# tangnano9k-bob-adapter.net
KiCad netlist of a schematic drawn in EAGLE
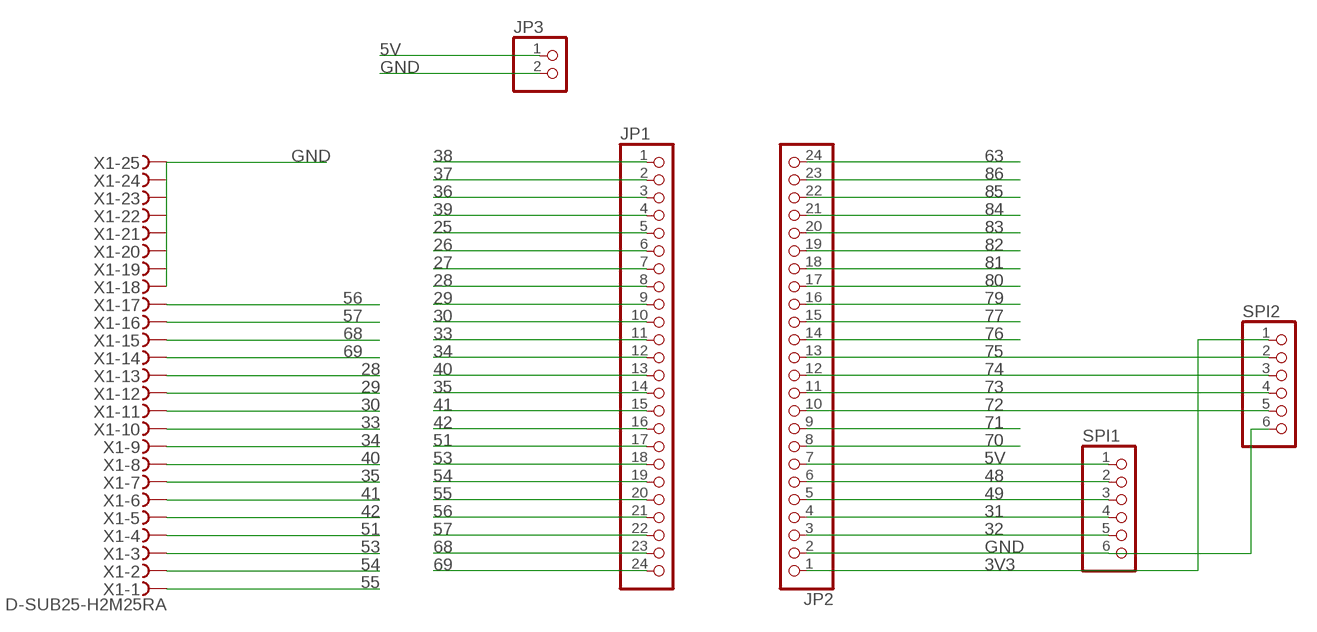
[diagram p0: schematic, sheet 1]

(export (version "E")
  (design (tool "Eeschema 10.0.6"))
  (components
    (comp (ref "JP1")
      (value "PINHD-1X24")
      (footprint "eagle-import:1X24")
      (libsource (lib "eagle-import") (part "PINHD-1X24"))
    )
    (comp (ref "JP2")
      (value "PINHD-1X24")
      (footprint "eagle-import:1X24")
      (libsource (lib "eagle-import") (part "PINHD-1X24"))
    )
    (comp (ref "JP3")
      (value "PINHD-1X2")
      (footprint "eagle-import:1X02")
      (libsource (lib "eagle-import") (part "PINHD-1X2"))
    )
    (comp (ref "SPI1")
      (value "PINHD-1X6")
      (footprint "eagle-import:1X06")
      (libsource (lib "eagle-import") (part "PINHD-1X6"))
    )
    (comp (ref "SPI2")
      (value "PINHD-1X6")
      (footprint "eagle-import:1X06")
      (libsource (lib "eagle-import") (part "PINHD-1X6"))
    )
    (comp (ref "X1")
      (value "D-SUB25-H2M25RA")
      (footprint "eagle-import:H2M25RA")
      (libsource (lib "eagle-import") (part "D-SUB25-H2M25RA"))
    )
  )
  (nets
    (net (code "1") (name "/3V3") (class "Default")
      (node (ref "JP2") (pin "1") (pinfunction "1_1") (pintype "passive"))
      (node (ref "SPI2") (pin "1") (pinfunction "1_1") (pintype "passive"))
    )
    (net (code "2") (name "/5V") (class "Default")
      (node (ref "JP2") (pin "7") (pinfunction "7_7") (pintype "passive"))
      (node (ref "JP3") (pin "1") (pinfunction "1_1") (pintype "passive"))
      (node (ref "SPI1") (pin "1") (pinfunction "1_1") (pintype "passive"))
    )
    (net (code "3") (name "/25") (class "Default")
      (node (ref "JP1") (pin "5") (pinfunction "5_5") (pintype "passive"))
    )
    (net (code "4") (name "/26") (class "Default")
      (node (ref "JP1") (pin "6") (pinfunction "6_6") (pintype "passive"))
    )
    (net (code "5") (name "/27") (class "Default")
      (node (ref "JP1") (pin "7") (pinfunction "7_7") (pintype "passive"))
    )
    (net (code "6") (name "/28") (class "Default")
      (node (ref "JP1") (pin "8") (pinfunction "8_8") (pintype "passive"))
      (node (ref "X1") (pin "13") (pinfunction "F_13") (pintype "passive"))
    )
    (net (code "7") (name "/29") (class "Default")
      (node (ref "JP1") (pin "9") (pinfunction "9_9") (pintype "passive"))
      (node (ref "X1") (pin "12") (pinfunction "F_12") (pintype "passive"))
    )
    (net (code "8") (name "/30") (class "Default")
      (node (ref "JP1") (pin "10") (pinfunction "10_10") (pintype "passive"))
      (node (ref "X1") (pin "11") (pinfunction "F_11") (pintype "passive"))
    )
    (net (code "9") (name "/31") (class "Default")
      (node (ref "JP2") (pin "4") (pinfunction "4_4") (pintype "passive"))
      (node (ref "SPI1") (pin "4") (pinfunction "4_4") (pintype "passive"))
    )
    (net (code "10") (name "/32") (class "Default")
      (node (ref "JP2") (pin "3") (pinfunction "3_3") (pintype "passive"))
      (node (ref "SPI1") (pin "5") (pinfunction "5_5") (pintype "passive"))
    )
    (net (code "11") (name "/33") (class "Default")
      (node (ref "JP1") (pin "11") (pinfunction "11_11") (pintype "passive"))
      (node (ref "X1") (pin "10") (pinfunction "F_10") (pintype "passive"))
    )
    (net (code "12") (name "/34") (class "Default")
      (node (ref "JP1") (pin "12") (pinfunction "12_12") (pintype "passive"))
      (node (ref "X1") (pin "9") (pinfunction "F_9") (pintype "passive"))
    )
    (net (code "13") (name "/35") (class "Default")
      (node (ref "JP1") (pin "14") (pinfunction "14_14") (pintype "passive"))
      (node (ref "X1") (pin "7") (pinfunction "F_7") (pintype "passive"))
    )
    (net (code "14") (name "/36") (class "Default")
      (node (ref "JP1") (pin "3") (pinfunction "3_3") (pintype "passive"))
    )
    (net (code "15") (name "/37") (class "Default")
      (node (ref "JP1") (pin "2") (pinfunction "2_2") (pintype "passive"))
    )
    (net (code "16") (name "/38") (class "Default")
      (node (ref "JP1") (pin "1") (pinfunction "1_1") (pintype "passive"))
    )
    (net (code "17") (name "/39") (class "Default")
      (node (ref "JP1") (pin "4") (pinfunction "4_4") (pintype "passive"))
    )
    (net (code "18") (name "/40") (class "Default")
      (node (ref "JP1") (pin "13") (pinfunction "13_13") (pintype "passive"))
      (node (ref "X1") (pin "8") (pinfunction "F_8") (pintype "passive"))
    )
    (net (code "19") (name "/41") (class "Default")
      (node (ref "JP1") (pin "15") (pinfunction "15_15") (pintype "passive"))
      (node (ref "X1") (pin "6") (pinfunction "F_6") (pintype "passive"))
    )
    (net (code "20") (name "/42") (class "Default")
      (node (ref "JP1") (pin "16") (pinfunction "16_16") (pintype "passive"))
      (node (ref "X1") (pin "5") (pinfunction "F_5") (pintype "passive"))
    )
    (net (code "21") (name "/48") (class "Default")
      (node (ref "JP2") (pin "6") (pinfunction "6_6") (pintype "passive"))
      (node (ref "SPI1") (pin "2") (pinfunction "2_2") (pintype "passive"))
    )
    (net (code "22") (name "/49") (class "Default")
      (node (ref "JP2") (pin "5") (pinfunction "5_5") (pintype "passive"))
      (node (ref "SPI1") (pin "3") (pinfunction "3_3") (pintype "passive"))
    )
    (net (code "23") (name "/51") (class "Default")
      (node (ref "JP1") (pin "17") (pinfunction "17_17") (pintype "passive"))
      (node (ref "X1") (pin "4") (pinfunction "F_4") (pintype "passive"))
    )
    (net (code "24") (name "/53") (class "Default")
      (node (ref "JP1") (pin "18") (pinfunction "18_18") (pintype "passive"))
      (node (ref "X1") (pin "3") (pinfunction "F_3") (pintype "passive"))
    )
    (net (code "25") (name "/54") (class "Default")
      (node (ref "JP1") (pin "19") (pinfunction "19_19") (pintype "passive"))
      (node (ref "X1") (pin "2") (pinfunction "F_2") (pintype "passive"))
    )
    (net (code "26") (name "/55") (class "Default")
      (node (ref "JP1") (pin "20") (pinfunction "20_20") (pintype "passive"))
      (node (ref "X1") (pin "1") (pinfunction "F_1") (pintype "passive"))
    )
    (net (code "27") (name "/56") (class "Default")
      (node (ref "JP1") (pin "21") (pinfunction "21_21") (pintype "passive"))
      (node (ref "X1") (pin "17") (pinfunction "F_17") (pintype "passive"))
    )
    (net (code "28") (name "/57") (class "Default")
      (node (ref "JP1") (pin "22") (pinfunction "22_22") (pintype "passive"))
      (node (ref "X1") (pin "16") (pinfunction "F_16") (pintype "passive"))
    )
    (net (code "29") (name "/63") (class "Default")
      (node (ref "JP2") (pin "24") (pinfunction "24_24") (pintype "passive"))
    )
    (net (code "30") (name "/68") (class "Default")
      (node (ref "JP1") (pin "23") (pinfunction "23_23") (pintype "passive"))
      (node (ref "X1") (pin "15") (pinfunction "F_15") (pintype "passive"))
    )
    (net (code "31") (name "/69") (class "Default")
      (node (ref "JP1") (pin "24") (pinfunction "24_24") (pintype "passive"))
      (node (ref "X1") (pin "14") (pinfunction "F_14") (pintype "passive"))
    )
    (net (code "32") (name "/70") (class "Default")
      (node (ref "JP2") (pin "8") (pinfunction "8_8") (pintype "passive"))
    )
    (net (code "33") (name "/71") (class "Default")
      (node (ref "JP2") (pin "9") (pinfunction "9_9") (pintype "passive"))
    )
    (net (code "34") (name "/72") (class "Default")
      (node (ref "JP2") (pin "10") (pinfunction "10_10") (pintype "passive"))
      (node (ref "SPI2") (pin "5") (pinfunction "5_5") (pintype "passive"))
    )
    (net (code "35") (name "/73") (class "Default")
      (node (ref "JP2") (pin "11") (pinfunction "11_11") (pintype "passive"))
      (node (ref "SPI2") (pin "4") (pinfunction "4_4") (pintype "passive"))
    )
    (net (code "36") (name "/74") (class "Default")
      (node (ref "JP2") (pin "12") (pinfunction "12_12") (pintype "passive"))
      (node (ref "SPI2") (pin "3") (pinfunction "3_3") (pintype "passive"))
    )
    (net (code "37") (name "/75") (class "Default")
      (node (ref "JP2") (pin "13") (pinfunction "13_13") (pintype "passive"))
      (node (ref "SPI2") (pin "2") (pinfunction "2_2") (pintype "passive"))
    )
    (net (code "38") (name "/76") (class "Default")
      (node (ref "JP2") (pin "14") (pinfunction "14_14") (pintype "passive"))
    )
    (net (code "39") (name "/77") (class "Default")
      (node (ref "JP2") (pin "15") (pinfunction "15_15") (pintype "passive"))
    )
    (net (code "40") (name "/79") (class "Default")
      (node (ref "JP2") (pin "16") (pinfunction "16_16") (pintype "passive"))
    )
    (net (code "41") (name "/80") (class "Default")
      (node (ref "JP2") (pin "17") (pinfunction "17_17") (pintype "passive"))
    )
    (net (code "42") (name "/81") (class "Default")
      (node (ref "JP2") (pin "18") (pinfunction "18_18") (pintype "passive"))
    )
    (net (code "43") (name "/82") (class "Default")
      (node (ref "JP2") (pin "19") (pinfunction "19_19") (pintype "passive"))
    )
    (net (code "44") (name "/83") (class "Default")
      (node (ref "JP2") (pin "20") (pinfunction "20_20") (pintype "passive"))
    )
    (net (code "45") (name "/84") (class "Default")
      (node (ref "JP2") (pin "21") (pinfunction "21_21") (pintype "passive"))
    )
    (net (code "46") (name "/85") (class "Default")
      (node (ref "JP2") (pin "22") (pinfunction "22_22") (pintype "passive"))
    )
    (net (code "47") (name "/86") (class "Default")
      (node (ref "JP2") (pin "23") (pinfunction "23_23") (pintype "passive"))
    )
    (net (code "48") (name "/GND") (class "Default")
      (node (ref "JP2") (pin "2") (pinfunction "2_2") (pintype "passive"))
      (node (ref "JP3") (pin "2") (pinfunction "2_2") (pintype "passive"))
      (node (ref "SPI1") (pin "6") (pinfunction "6_6") (pintype "passive"))
      (node (ref "SPI2") (pin "6") (pinfunction "6_6") (pintype "passive"))
      (node (ref "X1") (pin "18") (pinfunction "F_18") (pintype "passive"))
      (node (ref "X1") (pin "19") (pinfunction "F_19") (pintype "passive"))
      (node (ref "X1") (pin "20") (pinfunction "F_20") (pintype "passive"))
      (node (ref "X1") (pin "21") (pinfunction "F_21") (pintype "passive"))
      (node (ref "X1") (pin "22") (pinfunction "F_22") (pintype "passive"))
      (node (ref "X1") (pin "23") (pinfunction "F_23") (pintype "passive"))
      (node (ref "X1") (pin "24") (pinfunction "F_24") (pintype "passive"))
      (node (ref "X1") (pin "25") (pinfunction "F_25") (pintype "passive"))
    )
  )
)
